# 01_CMUT_TX.net
KiCad netlist of a schematic drawn in Altium Designer
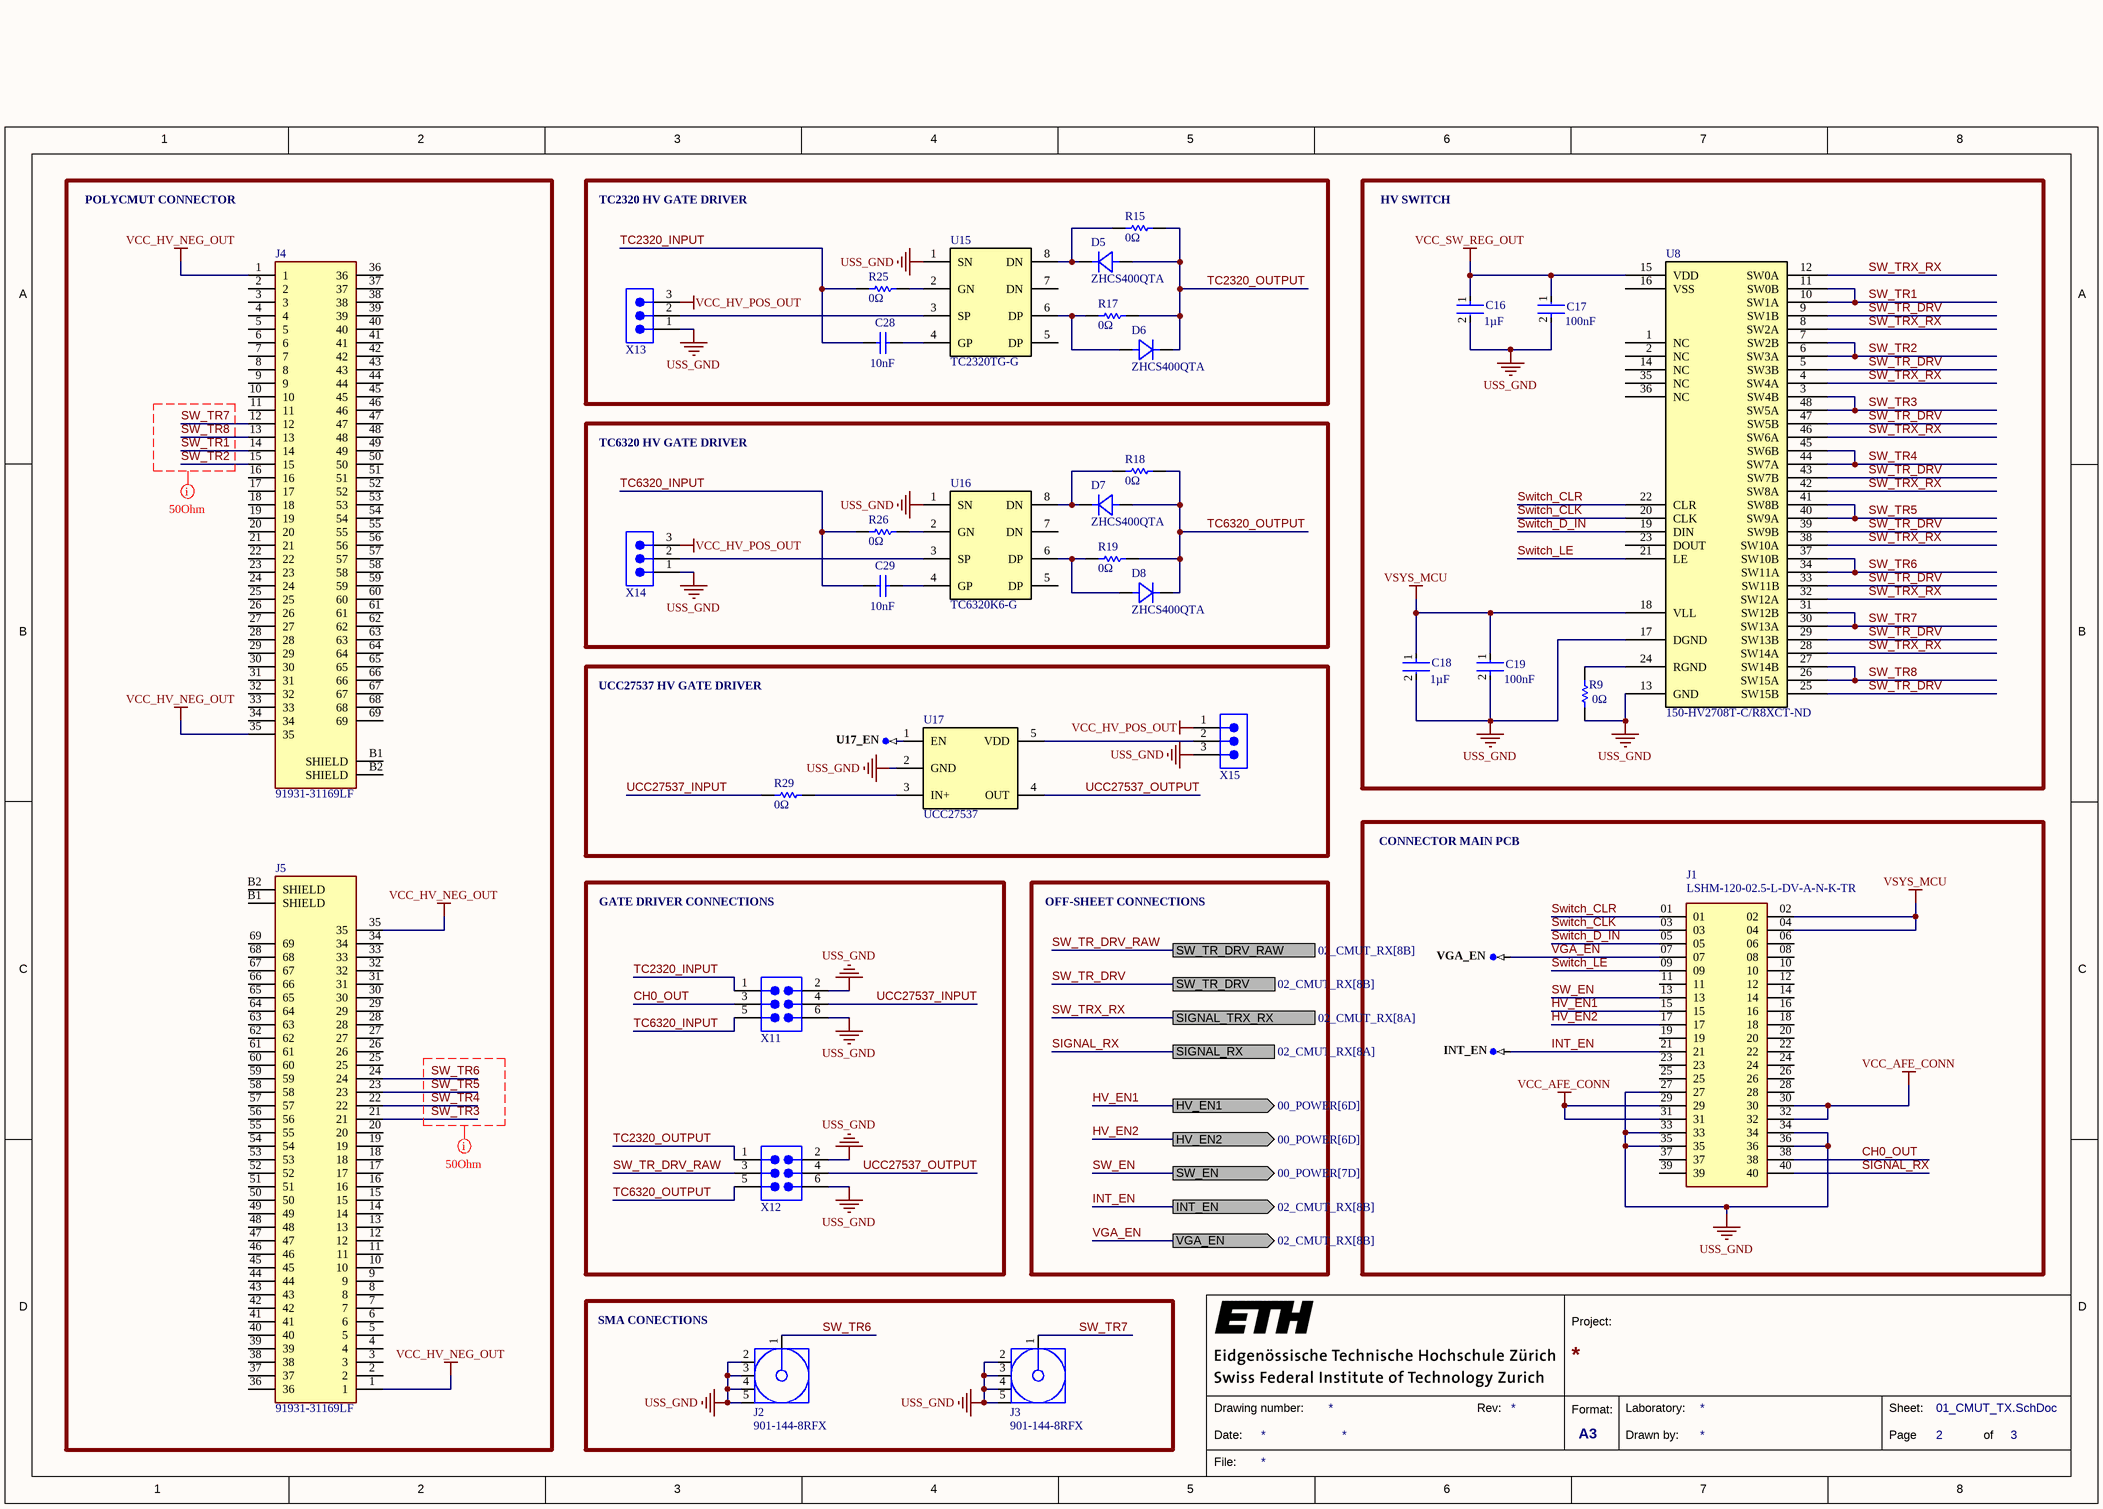
[diagram p0: 01_CMUT_TX.SchDoc]

(export (version "E")
  (design (tool "Eeschema 10.0.6"))
  (components
    (comp (ref "C16")
      (value "CGA3E3X5R1H105K")
      (footprint "FP-CGA3E-0_3-0_1-IPC_B")
      (description "Cap Ceramic 1uF 50V X5R 10% Pad SMD 0603 +85°C Automotive T/R")
      (fields (field (name "TOLERANCE") "10%") (field (name "CAPACITANCE") "1µF"))
      (libsource (lib "Altium Content Vault") (part "b4654b650e69147ec39a6b967a45e02"))
    )
    (comp (ref "C17")
      (value "C1608X5R1H104K080AA")
      (footprint "FP-C1608-080-0_1-MFG")
      (description "Multilayer Ceramic Capacitors 100nF ±10% 50V X5R SMD 0603")
      (fields (field (name "TOLERANCE") "10%") (field (name "CAPACITANCE") "100nF"))
      (libsource (lib "Altium Content Vault") (part "236180d848d6139a670b325ea6854c9"))
    )
    (comp (ref "C18")
      (value "CGA3E3X5R1H105K")
      (footprint "FP-CGA3E-0_3-0_1-IPC_B")
      (description "Cap Ceramic 1uF 50V X5R 10% Pad SMD 0603 +85°C Automotive T/R")
      (fields (field (name "TOLERANCE") "10%") (field (name "CAPACITANCE") "1µF"))
      (libsource (lib "Altium Content Vault") (part "b4654b650e69147ec39a6b967a45e02"))
    )
    (comp (ref "C19")
      (value "C1608X5R1H104K080AA")
      (footprint "FP-C1608-080-0_1-MFG")
      (description "Multilayer Ceramic Capacitors 100nF ±10% 50V X5R SMD 0603")
      (fields (field (name "TOLERANCE") "10%") (field (name "CAPACITANCE") "100nF"))
      (libsource (lib "Altium Content Vault") (part "236180d848d6139a670b325ea6854c9"))
    )
    (comp (ref "C28")
      (value "06035D103KAT2A")
      (footprint "CAPC1608X90X35NL15T15")
      (fields (field (name "MANUFACTURER") "AVX Interconnect / Elco") (field (name "CAPACITANCE") "10nF"))
      (libsource (lib "Altium Content Vault") (part "CAP"))
    )
    (comp (ref "C29")
      (value "06035D103KAT2A")
      (footprint "CAPC1608X90X35NL15T15")
      (fields (field (name "MANUFACTURER") "AVX Interconnect / Elco") (field (name "CAPACITANCE") "10nF"))
      (libsource (lib "Altium Content Vault") (part "CAP"))
    )
    (comp (ref "D5")
      (value "ZHCS400QTA")
      (footprint "DIODE_SOD323_DIO")
      (description "Diode Schottky 40V 1A Automotive 2-Pin SOD-323 T/R")
      (fields (field (name "MANUFACTURER") "Diodes"))
      (libsource (lib "Schlib1") (part "ZHCS400QTA"))
    )
    (comp (ref "D6")
      (value "ZHCS400QTA")
      (footprint "DIODE_SOD323_DIO")
      (description "Diode Schottky 40V 1A Automotive 2-Pin SOD-323 T/R")
      (fields (field (name "MANUFACTURER") "Diodes"))
      (libsource (lib "Schlib1") (part "ZHCS400QTA"))
    )
    (comp (ref "D7")
      (value "ZHCS400QTA")
      (footprint "DIODE_SOD323_DIO")
      (description "Diode Schottky 40V 1A Automotive 2-Pin SOD-323 T/R")
      (fields (field (name "MANUFACTURER") "Diodes"))
      (libsource (lib "Schlib1") (part "ZHCS400QTA"))
    )
    (comp (ref "D8")
      (value "ZHCS400QTA")
      (footprint "DIODE_SOD323_DIO")
      (description "Diode Schottky 40V 1A Automotive 2-Pin SOD-323 T/R")
      (fields (field (name "MANUFACTURER") "Diodes"))
      (libsource (lib "Schlib1") (part "ZHCS400QTA"))
    )
    (comp (ref "INT_EN")
      (value "TP-SM-C-100")
      (footprint "TP-SM-C-100")
      (description "Test Point, Surface Mount, Circular, Pad Diameter 1 mm")
      (fields (field (name "MANUFACTURER") "No Vendor"))
      (libsource (lib "Altium Content Vault") (part "TP-SM"))
    )
    (comp (ref "J1")
      (value "LSHM-120-02.5-L-DV-A-N-K-TR")
      (footprint "SAMTEC_LSHM-120-XX.X-X-DV-A-N-XX")
      (description "Conn Socket and Terminal Strip HDR/SKT 40 POS 0.5mm Solder ST SMD T/R")
      (fields
        (field (name "MANUFACTURER") "Samtec")
        (field (name "MANUFACTURER PART NUMBER") "LSHM-120-02.5-L-DV-A-N-K-TR")
      )
      (libsource (lib "Schlib1") (part "LSHM-120-02.5-L-DV-A-N-K-TR"))
    )
    (comp (ref "J2")
      (value "901-144-8RFX")
      (footprint "AMPH-901-144-8RFX_V")
      (description "Coaxial Connector, 18 GHz, 50 Ohm, -65 to 165 degC, 5-Pin THD, RoHS, Bulk")
      (fields (field (name "MANUFACTURER") "Amphenol"))
      (libsource (lib "Altium Content Vault") (part "CN-S-4F-RF5"))
    )
    (comp (ref "J3")
      (value "901-144-8RFX")
      (footprint "AMPH-901-144-8RFX_V")
      (description "Coaxial Connector, 18 GHz, 50 Ohm, -65 to 165 degC, 5-Pin THD, RoHS, Bulk")
      (fields (field (name "MANUFACTURER") "Amphenol"))
      (libsource (lib "Altium Content Vault") (part "CN-S-4F-RF5"))
    )
    (comp (ref "J4")
      (value "91931-31169LF")
      (footprint "FRAMETOME_91931-31169LF")
      (description "Conn; Rect; Industrial; MezzanineRECP; 69Cnts; SMT; I-IndustrialSeries")
      (libsource (lib "") (part "91931-31169LF_1"))
    )
    (comp (ref "J5")
      (value "91931-31169LF")
      (footprint "FRAMETOME_91931-31169LF")
      (description "Conn; Rect; Industrial; MezzanineRECP; 69Cnts; SMT; I-IndustrialSeries")
      (libsource (lib "91931-31169LF") (part "91931-31169LF"))
    )
    (comp (ref "R9")
      (value "RC0603JR-130RL")
      (footprint "RESC1608X55X25NL10T15")
      (fields (field (name "MANUFACTURER") "Yageo") (field (name "RESISTANCE") "0Ω"))
      (libsource (lib "Altium Content Vault") (part "RES"))
    )
    (comp (ref "R15")
      (value "RC0603JR-130RL")
      (footprint "RESC1608X55X25NL10T15")
      (fields (field (name "MANUFACTURER") "Yageo") (field (name "RESISTANCE") "0Ω"))
      (libsource (lib "Altium Content Vault") (part "RES"))
    )
    (comp (ref "R17")
      (value "RC0603JR-130RL")
      (footprint "RESC1608X55X25NL10T15")
      (fields (field (name "MANUFACTURER") "Yageo") (field (name "RESISTANCE") "0Ω"))
      (libsource (lib "Altium Content Vault") (part "RES"))
    )
    (comp (ref "R18")
      (value "RC0603JR-130RL")
      (footprint "RESC1608X55X25NL10T15")
      (fields (field (name "MANUFACTURER") "Yageo") (field (name "RESISTANCE") "0Ω"))
      (libsource (lib "Altium Content Vault") (part "RES"))
    )
    (comp (ref "R19")
      (value "RC0603JR-130RL")
      (footprint "RESC1608X55X25NL10T15")
      (fields (field (name "MANUFACTURER") "Yageo") (field (name "RESISTANCE") "0Ω"))
      (libsource (lib "Altium Content Vault") (part "RES"))
    )
    (comp (ref "R25")
      (value "RC0603JR-130RL")
      (footprint "RESC1608X55X25NL10T15")
      (fields (field (name "MANUFACTURER") "Yageo") (field (name "RESISTANCE") "0Ω"))
      (libsource (lib "Altium Content Vault") (part "RES"))
    )
    (comp (ref "R26")
      (value "RC0603JR-130RL")
      (footprint "RESC1608X55X25NL10T15")
      (fields (field (name "MANUFACTURER") "Yageo") (field (name "RESISTANCE") "0Ω"))
      (libsource (lib "Altium Content Vault") (part "RES"))
    )
    (comp (ref "R29")
      (value "RC0603JR-130RL")
      (footprint "RESC1608X55X25NL10T15")
      (fields (field (name "MANUFACTURER") "Yageo") (field (name "RESISTANCE") "0Ω"))
      (libsource (lib "Altium Content Vault") (part "RES"))
    )
    (comp (ref "U8")
      (value "HV2708T-C/R8X")
      (footprint "LQFP48_7X7MC_MCH")
      (description "16-CH 200V No Hv Bias Switch (SPST), 1 Bleed Resistor 48 LQFP 7X7X1.4MM T/r Rohs Compliant: Yes")
      (fields
        (field (name "MANUFACTURER") "Microchip")
        (field (name "SUPPLIER PART NUMBER 1") "150-HV2708T-C/R8XCT-ND")
      )
      (libsource (lib "Schlib1") (part "HV2708T-C/R8X"))
    )
    (comp (ref "U15")
      (value "TC2320TG-G")
      (footprint "SOIC127P599X173-8N")
      (description "8L SOIC N-Channel and P-Channel Enhancement-Mode Dual MOSFET")
      (libsource (lib "Schlib1") (part "TC2320"))
    )
    (comp (ref "U16")
      (value "TC6320K6-G")
      (footprint "SOIC127P599X173-8N")
      (description "8L SOIC N-Channel and P-Channel Enhancement-Mode Dual MOSFET")
      (libsource (lib "Schlib1") (part "TC2320"))
    )
    (comp (ref "U17")
      (value "UCC27537")
      (footprint "SOT95P280X145-5N")
      (description "5P SOT-23 DBV MOSFET IGBT Single-Gate-Driver")
      (libsource (lib "Schlib1") (part "UCC27537"))
    )
    (comp (ref "U17_EN")
      (value "TP-SM-C-100")
      (footprint "TP-SM-C-100")
      (description "Test Point, Surface Mount, Circular, Pad Diameter 1 mm")
      (fields (field (name "MANUFACTURER") "No Vendor"))
      (libsource (lib "Altium Content Vault") (part "TP-SM"))
    )
    (comp (ref "VGA_EN")
      (value "TP-SM-C-100")
      (footprint "TP-SM-C-100")
      (description "Test Point, Surface Mount, Circular, Pad Diameter 1 mm")
      (fields (field (name "MANUFACTURER") "No Vendor"))
      (libsource (lib "Altium Content Vault") (part "TP-SM"))
    )
    (comp (ref "X11")
      (value "67996-106HLF")
      (footprint "67996-106HLF")
      (description "6 Positions Header, Unshrouded Connector 0.100\" (2.54mm) Through Hole Gold or Gold, GXT™")
      (fields (field (name "MANUFACTURER") "Amphenol FCI"))
      (libsource (lib "ETHZ Vault") (part "CON-3x2-Male"))
    )
    (comp (ref "X12")
      (value "67996-106HLF")
      (footprint "67996-106HLF")
      (description "6 Positions Header, Unshrouded Connector 0.100\" (2.54mm) Through Hole Gold or Gold, GXT™")
      (fields (field (name "MANUFACTURER") "Amphenol FCI"))
      (libsource (lib "ETHZ Vault") (part "CON-3x2-Male"))
    )
    (comp (ref "X13")
      (value "68000-103HLF")
      (footprint "68000-103HLF")
      (description "3 Positions Header, Unshrouded Connector 0.100\" (2.54mm) Through Hole Gold or Gold, GXT™")
      (fields (field (name "MANUFACTURER") "Amphenol FCI"))
      (libsource (lib "ETHZ Vault") (part "CON-1x3-Male"))
    )
    (comp (ref "X14")
      (value "68000-103HLF")
      (footprint "68000-103HLF")
      (description "3 Positions Header, Unshrouded Connector 0.100\" (2.54mm) Through Hole Gold or Gold, GXT™")
      (fields (field (name "MANUFACTURER") "Amphenol FCI"))
      (libsource (lib "ETHZ Vault") (part "CON-1x3-Male"))
    )
    (comp (ref "X15")
      (value "68000-103HLF")
      (footprint "68000-103HLF")
      (description "3 Positions Header, Unshrouded Connector 0.100\" (2.54mm) Through Hole Gold or Gold, GXT™")
      (fields (field (name "MANUFACTURER") "Amphenol FCI"))
      (libsource (lib "ETHZ Vault") (part "CON-1x3-Male"))
    )
  )
  (nets
    (net (code "2") (name "/CH0_OUT") (class "Default")
      (node (ref "J1") (pin "38") (pinfunction "38_38") (pintype "passive"))
      (node (ref "X11") (pin "3") (pinfunction "3_3") (pintype "passive"))
    )
    (net (code "3") (name "/HV_EN1") (class "Default")
      (node (ref "J1") (pin "15") (pinfunction "15_15") (pintype "passive"))
    )
    (net (code "4") (name "/HV_EN2") (class "Default")
      (node (ref "J1") (pin "17") (pinfunction "17_17") (pintype "passive"))
    )
    (net (code "5") (name "/INT_EN") (class "Default")
      (node (ref "INT_EN") (pin "1") (pinfunction "1_1") (pintype "input"))
      (node (ref "J1") (pin "21") (pinfunction "21_21") (pintype "passive"))
    )
    (net (code "6") (name "/SIGNAL_RX") (class "Default")
      (node (ref "J1") (pin "40") (pinfunction "40_40") (pintype "passive"))
    )
    (net (code "7") (name "/SW_EN") (class "Default")
      (node (ref "J1") (pin "13") (pinfunction "13_13") (pintype "passive"))
    )
    (net (code "8") (name "/SW_TR1") (class "Default")
      (node (ref "J4") (pin "14") (pinfunction "14_14") (pintype "passive"))
      (node (ref "U8") (pin "10") (pinfunction "SW1A_10") (pintype "passive"))
      (node (ref "U8") (pin "11") (pinfunction "SW0B_11") (pintype "passive"))
    )
    (net (code "9") (name "/SW_TR2") (class "Default")
      (node (ref "J4") (pin "15") (pinfunction "15_15") (pintype "passive"))
      (node (ref "U8") (pin "6") (pinfunction "SW3A_6") (pintype "passive"))
      (node (ref "U8") (pin "7") (pinfunction "SW2B_7") (pintype "passive"))
    )
    (net (code "10") (name "/SW_TR3") (class "Default")
      (node (ref "J5") (pin "21") (pinfunction "21_21") (pintype "passive"))
      (node (ref "U8") (pin "3") (pinfunction "SW4B_3") (pintype "passive"))
      (node (ref "U8") (pin "48") (pinfunction "SW5A_48") (pintype "passive"))
    )
    (net (code "11") (name "/SW_TR4") (class "Default")
      (node (ref "J5") (pin "22") (pinfunction "22_22") (pintype "passive"))
      (node (ref "U8") (pin "44") (pinfunction "SW7A_44") (pintype "passive"))
      (node (ref "U8") (pin "45") (pinfunction "SW6B_45") (pintype "passive"))
    )
    (net (code "12") (name "/SW_TR5") (class "Default")
      (node (ref "J5") (pin "23") (pinfunction "23_23") (pintype "passive"))
      (node (ref "U8") (pin "40") (pinfunction "SW9A_40") (pintype "passive"))
      (node (ref "U8") (pin "41") (pinfunction "SW8B_41") (pintype "passive"))
    )
    (net (code "13") (name "/SW_TR6") (class "Default")
      (node (ref "J2") (pin "1") (pinfunction "1_1") (pintype "passive"))
      (node (ref "J5") (pin "24") (pinfunction "24_24") (pintype "passive"))
      (node (ref "U8") (pin "34") (pinfunction "SW11A_34") (pintype "passive"))
      (node (ref "U8") (pin "37") (pinfunction "SW10B_37") (pintype "passive"))
    )
    (net (code "14") (name "/SW_TR7") (class "Default")
      (node (ref "J3") (pin "1") (pinfunction "1_1") (pintype "passive"))
      (node (ref "J4") (pin "12") (pinfunction "12_12") (pintype "passive"))
      (node (ref "U8") (pin "30") (pinfunction "SW13A_30") (pintype "passive"))
      (node (ref "U8") (pin "31") (pinfunction "SW12B_31") (pintype "passive"))
    )
    (net (code "15") (name "/SW_TR8") (class "Default")
      (node (ref "J4") (pin "13") (pinfunction "13_13") (pintype "passive"))
      (node (ref "U8") (pin "26") (pinfunction "SW15A_26") (pintype "passive"))
      (node (ref "U8") (pin "27") (pinfunction "SW14B_27") (pintype "passive"))
    )
    (net (code "16") (name "/SW_TRX_RX") (class "Default")
      (node (ref "U8") (pin "12") (pinfunction "SW0A_12") (pintype "passive"))
      (node (ref "U8") (pin "28") (pinfunction "SW14A_28") (pintype "passive"))
      (node (ref "U8") (pin "32") (pinfunction "SW12A_32") (pintype "passive"))
      (node (ref "U8") (pin "38") (pinfunction "SW10A_38") (pintype "passive"))
      (node (ref "U8") (pin "4") (pinfunction "SW4A_4") (pintype "passive"))
      (node (ref "U8") (pin "42") (pinfunction "SW8A_42") (pintype "passive"))
      (node (ref "U8") (pin "46") (pinfunction "SW6A_46") (pintype "passive"))
      (node (ref "U8") (pin "8") (pinfunction "SW2A_8") (pintype "passive"))
    )
    (net (code "17") (name "/SW_TR_DRV") (class "Default")
      (node (ref "U8") (pin "25") (pinfunction "SW15B_25") (pintype "passive"))
      (node (ref "U8") (pin "29") (pinfunction "SW13B_29") (pintype "passive"))
      (node (ref "U8") (pin "33") (pinfunction "SW11B_33") (pintype "passive"))
      (node (ref "U8") (pin "39") (pinfunction "SW9B_39") (pintype "passive"))
      (node (ref "U8") (pin "43") (pinfunction "SW7B_43") (pintype "passive"))
      (node (ref "U8") (pin "47") (pinfunction "SW5B_47") (pintype "passive"))
      (node (ref "U8") (pin "5") (pinfunction "SW3B_5") (pintype "passive"))
      (node (ref "U8") (pin "9") (pinfunction "SW1B_9") (pintype "passive"))
    )
    (net (code "18") (name "/SW_TR_DRV_RAW") (class "Default")
      (node (ref "X12") (pin "3") (pinfunction "3_3") (pintype "passive"))
    )
    (net (code "19") (name "/Switch_CLK") (class "Default")
      (node (ref "J1") (pin "03") (pinfunction "03_03") (pintype "passive"))
      (node (ref "U8") (pin "20") (pinfunction "CLK_20") (pintype "passive"))
    )
    (net (code "20") (name "/Switch_CLR") (class "Default")
      (node (ref "J1") (pin "01") (pinfunction "01_01") (pintype "passive"))
      (node (ref "U8") (pin "22") (pinfunction "CLR_22") (pintype "passive"))
    )
    (net (code "21") (name "/Switch_D_IN") (class "Default")
      (node (ref "J1") (pin "05") (pinfunction "05_05") (pintype "passive"))
      (node (ref "U8") (pin "19") (pinfunction "DIN_19") (pintype "passive"))
    )
    (net (code "22") (name "/Switch_LE") (class "Default")
      (node (ref "J1") (pin "09") (pinfunction "09_09") (pintype "passive"))
      (node (ref "U8") (pin "21") (pinfunction "LE_21") (pintype "passive"))
    )
    (net (code "23") (name "/TC2320_INPUT") (class "Default")
      (node (ref "C28") (pin "1") (pinfunction "1_1") (pintype "passive"))
      (node (ref "R25") (pin "2") (pinfunction "2_2") (pintype "passive"))
      (node (ref "X11") (pin "1") (pinfunction "1_1") (pintype "passive"))
    )
    (net (code "24") (name "/TC2320_OUTPUT") (class "Default")
      (node (ref "D5") (pin "2") (pinfunction "2_2") (pintype "passive"))
      (node (ref "D6") (pin "1") (pinfunction "1_1") (pintype "passive"))
      (node (ref "R15") (pin "1") (pinfunction "1_1") (pintype "passive"))
      (node (ref "R17") (pin "1") (pinfunction "1_1") (pintype "passive"))
      (node (ref "X12") (pin "1") (pinfunction "1_1") (pintype "passive"))
    )
    (net (code "25") (name "/TC6320_INPUT") (class "Default")
      (node (ref "C29") (pin "1") (pinfunction "1_1") (pintype "passive"))
      (node (ref "R26") (pin "2") (pinfunction "2_2") (pintype "passive"))
      (node (ref "X11") (pin "5") (pinfunction "5_5") (pintype "passive"))
    )
    (net (code "26") (name "/TC6320_OUTPUT") (class "Default")
      (node (ref "D7") (pin "2") (pinfunction "2_2") (pintype "passive"))
      (node (ref "D8") (pin "1") (pinfunction "1_1") (pintype "passive"))
      (node (ref "R18") (pin "1") (pinfunction "1_1") (pintype "passive"))
      (node (ref "R19") (pin "1") (pinfunction "1_1") (pintype "passive"))
      (node (ref "X12") (pin "5") (pinfunction "5_5") (pintype "passive"))
    )
    (net (code "27") (name "/UCC27537_INPUT") (class "Default")
      (node (ref "R29") (pin "2") (pinfunction "2_2") (pintype "passive"))
      (node (ref "X11") (pin "4") (pinfunction "4_4") (pintype "passive"))
    )
    (net (code "28") (name "/UCC27537_OUTPUT") (class "Default")
      (node (ref "U17") (pin "4") (pinfunction "OUT_4") (pintype "power_in"))
      (node (ref "X12") (pin "4") (pinfunction "4_4") (pintype "passive"))
    )
    (net (code "29") (name "/VGA_EN") (class "Default")
      (node (ref "J1") (pin "07") (pinfunction "07_07") (pintype "passive"))
      (node (ref "VGA_EN") (pin "1") (pinfunction "1_1") (pintype "input"))
    )
    (net (code "30") (name "Net-(D5-Pad1)") (class "Default")
      (node (ref "D5") (pin "1") (pinfunction "1_1") (pintype "passive"))
      (node (ref "R15") (pin "2") (pinfunction "2_2") (pintype "passive"))
      (node (ref "U15") (pin "8") (pinfunction "DN_8") (pintype "power_in"))
    )
    (net (code "31") (name "Net-(D6-Pad2)") (class "Default")
      (node (ref "D6") (pin "2") (pinfunction "2_2") (pintype "passive"))
      (node (ref "R17") (pin "2") (pinfunction "2_2") (pintype "passive"))
      (node (ref "U15") (pin "6") (pinfunction "DP_6") (pintype "power_in"))
    )
    (net (code "32") (name "Net-(D7-Pad1)") (class "Default")
      (node (ref "D7") (pin "1") (pinfunction "1_1") (pintype "passive"))
      (node (ref "R18") (pin "2") (pinfunction "2_2") (pintype "passive"))
      (node (ref "U16") (pin "8") (pinfunction "DN_8") (pintype "power_in"))
    )
    (net (code "33") (name "Net-(D8-Pad2)") (class "Default")
      (node (ref "D8") (pin "2") (pinfunction "2_2") (pintype "passive"))
      (node (ref "R19") (pin "2") (pinfunction "2_2") (pintype "passive"))
      (node (ref "U16") (pin "6") (pinfunction "DP_6") (pintype "power_in"))
    )
    (net (code "34") (name "Net-(U8-RGND)") (class "Default")
      (node (ref "R9") (pin "2") (pinfunction "2_2") (pintype "passive"))
      (node (ref "U8") (pin "24") (pinfunction "RGND_24") (pintype "passive"))
    )
    (net (code "35") (name "Net-(U15-GN)") (class "Default")
      (node (ref "R25") (pin "1") (pinfunction "1_1") (pintype "passive"))
      (node (ref "U15") (pin "2") (pinfunction "GN_2") (pintype "power_in"))
    )
    (net (code "36") (name "Net-(U15-GP)") (class "Default")
      (node (ref "C28") (pin "2") (pinfunction "2_2") (pintype "passive"))
      (node (ref "U15") (pin "4") (pinfunction "GP_4") (pintype "open_collector"))
    )
    (net (code "37") (name "Net-(U15-SP)") (class "Default")
      (node (ref "U15") (pin "3") (pinfunction "SP_3") (pintype "power_in"))
      (node (ref "X13") (pin "2") (pinfunction "2_2") (pintype "passive"))
    )
    (net (code "38") (name "Net-(U16-GN)") (class "Default")
      (node (ref "R26") (pin "1") (pinfunction "1_1") (pintype "passive"))
      (node (ref "U16") (pin "2") (pinfunction "GN_2") (pintype "power_in"))
    )
    (net (code "39") (name "Net-(U16-GP)") (class "Default")
      (node (ref "C29") (pin "2") (pinfunction "2_2") (pintype "passive"))
      (node (ref "U16") (pin "4") (pinfunction "GP_4") (pintype "open_collector"))
    )
    (net (code "40") (name "Net-(U16-SP)") (class "Default")
      (node (ref "U16") (pin "3") (pinfunction "SP_3") (pintype "power_in"))
      (node (ref "X14") (pin "2") (pinfunction "2_2") (pintype "passive"))
    )
    (net (code "41") (name "Net-(U17-EN)") (class "Default")
      (node (ref "U17") (pin "1") (pinfunction "EN_1") (pintype "power_in"))
      (node (ref "U17_EN") (pin "1") (pinfunction "1_1") (pintype "input"))
    )
    (net (code "42") (name "Net-(U17-IN+)") (class "Default")
      (node (ref "R29") (pin "1") (pinfunction "1_1") (pintype "passive"))
      (node (ref "U17") (pin "3") (pinfunction "IN+_3") (pintype "power_in"))
    )
    (net (code "43") (name "Net-(U17-VDD)") (class "Default")
      (node (ref "U17") (pin "5") (pinfunction "VDD_5") (pintype "power_in"))
      (node (ref "X15") (pin "2") (pinfunction "2_2") (pintype "passive"))
    )
    (net (code "44") (name "USS_GND") (class "Default")
      (node (ref "C16") (pin "2") (pinfunction "2_2") (pintype "passive"))
      (node (ref "C17") (pin "2") (pinfunction "2_2") (pintype "passive"))
      (node (ref "C18") (pin "2") (pinfunction "2_2") (pintype "passive"))
      (node (ref "C19") (pin "2") (pinfunction "2_2") (pintype "passive"))
      (node (ref "J1") (pin "27") (pinfunction "27_27") (pintype "passive"))
      (node (ref "J1") (pin "33") (pinfunction "33_33") (pintype "passive"))
      (node (ref "J1") (pin "34") (pinfunction "34_34") (pintype "passive"))
      (node (ref "J1") (pin "35") (pinfunction "35_35") (pintype "passive"))
      (node (ref "J1") (pin "36") (pinfunction "36_36") (pintype "passive"))
      (node (ref "J2") (pin "2") (pinfunction "2_2") (pintype "passive"))
      (node (ref "J2") (pin "3") (pinfunction "3_3") (pintype "passive"))
      (node (ref "J2") (pin "4") (pinfunction "4_4") (pintype "passive"))
      (node (ref "J2") (pin "5") (pinfunction "5_5") (pintype "passive"))
      (node (ref "J3") (pin "2") (pinfunction "2_2") (pintype "passive"))
      (node (ref "J3") (pin "3") (pinfunction "3_3") (pintype "passive"))
      (node (ref "J3") (pin "4") (pinfunction "4_4") (pintype "passive"))
      (node (ref "J3") (pin "5") (pinfunction "5_5") (pintype "passive"))
      (node (ref "R9") (pin "1") (pinfunction "1_1") (pintype "passive"))
      (node (ref "U15") (pin "1") (pinfunction "SN_1") (pintype "power_in"))
      (node (ref "U16") (pin "1") (pinfunction "SN_1") (pintype "power_in"))
      (node (ref "U17") (pin "2") (pinfunction "GND_2") (pintype "power_in"))
      (node (ref "U8") (pin "13") (pinfunction "GND_13") (pintype "passive"))
      (node (ref "U8") (pin "17") (pinfunction "DGND_17") (pintype "passive"))
      (node (ref "X11") (pin "2") (pinfunction "2_2") (pintype "passive"))
      (node (ref "X11") (pin "6") (pinfunction "6_6") (pintype "passive"))
      (node (ref "X12") (pin "2") (pinfunction "2_2") (pintype "passive"))
      (node (ref "X12") (pin "6") (pinfunction "6_6") (pintype "passive"))
      (node (ref "X13") (pin "1") (pinfunction "1_1") (pintype "passive"))
      (node (ref "X14") (pin "1") (pinfunction "1_1") (pintype "passive"))
      (node (ref "X15") (pin "3") (pinfunction "3_3") (pintype "passive"))
    )
    (net (code "45") (name "VCC_AFE_CONN") (class "Default")
      (node (ref "J1") (pin "29") (pinfunction "29_29") (pintype "passive"))
      (node (ref "J1") (pin "30") (pinfunction "30_30") (pintype "passive"))
      (node (ref "J1") (pin "31") (pinfunction "31_31") (pintype "passive"))
      (node (ref "J1") (pin "32") (pinfunction "32_32") (pintype "passive"))
    )
    (net (code "46") (name "VCC_HV_NEG_OUT") (class "Default")
      (node (ref "J4") (pin "1") (pinfunction "1_1") (pintype "passive"))
      (node (ref "J4") (pin "35") (pinfunction "35_35") (pintype "passive"))
      (node (ref "J5") (pin "1") (pinfunction "1_1") (pintype "passive"))
      (node (ref "J5") (pin "35") (pinfunction "35_35") (pintype "passive"))
    )
    (net (code "47") (name "VCC_HV_POS_OUT") (class "Default")
      (node (ref "X13") (pin "3") (pinfunction "3_3") (pintype "passive"))
      (node (ref "X14") (pin "3") (pinfunction "3_3") (pintype "passive"))
      (node (ref "X15") (pin "1") (pinfunction "1_1") (pintype "passive"))
    )
    (net (code "48") (name "VCC_SW_REG_OUT") (class "Default")
      (node (ref "C16") (pin "1") (pinfunction "1_1") (pintype "passive"))
      (node (ref "C17") (pin "1") (pinfunction "1_1") (pintype "passive"))
      (node (ref "U8") (pin "15") (pinfunction "VDD_15") (pintype "passive"))
    )
    (net (code "49") (name "VSYS_MCU") (class "Default")
      (node (ref "C18") (pin "1") (pinfunction "1_1") (pintype "passive"))
      (node (ref "C19") (pin "1") (pinfunction "1_1") (pintype "passive"))
      (node (ref "J1") (pin "02") (pinfunction "02_02") (pintype "passive"))
      (node (ref "J1") (pin "04") (pinfunction "04_04") (pintype "passive"))
      (node (ref "U8") (pin "18") (pinfunction "VLL_18") (pintype "passive"))
    )
    (net (code "50") (name "unconnected-(J1-Pad06)") (class "Default")
      (node (ref "J1") (pin "06") (pinfunction "06_06") (pintype "passive"))
    )
    (net (code "51") (name "unconnected-(J1-Pad08)") (class "Default")
      (node (ref "J1") (pin "08") (pinfunction "08_08") (pintype "passive"))
    )
    (net (code "52") (name "unconnected-(J1-Pad10)") (class "Default")
      (node (ref "J1") (pin "10") (pinfunction "10_10") (pintype "passive"))
    )
    (net (code "53") (name "unconnected-(J1-Pad11)") (class "Default")
      (node (ref "J1") (pin "11") (pinfunction "11_11") (pintype "passive"))
    )
    (net (code "54") (name "unconnected-(J1-Pad12)") (class "Default")
      (node (ref "J1") (pin "12") (pinfunction "12_12") (pintype "passive"))
    )
    (net (code "55") (name "unconnected-(J1-Pad14)") (class "Default")
      (node (ref "J1") (pin "14") (pinfunction "14_14") (pintype "passive"))
    )
    (net (code "56") (name "unconnected-(J1-Pad16)") (class "Default")
      (node (ref "J1") (pin "16") (pinfunction "16_16") (pintype "passive"))
    )
    (net (code "57") (name "unconnected-(J1-Pad18)") (class "Default")
      (node (ref "J1") (pin "18") (pinfunction "18_18") (pintype "passive"))
    )
    (net (code "58") (name "unconnected-(J1-Pad19)") (class "Default")
      (node (ref "J1") (pin "19") (pinfunction "19_19") (pintype "passive"))
    )
    (net (code "59") (name "unconnected-(J1-Pad20)") (class "Default")
      (node (ref "J1") (pin "20") (pinfunction "20_20") (pintype "passive"))
    )
    (net (code "60") (name "unconnected-(J1-Pad22)") (class "Default")
      (node (ref "J1") (pin "22") (pinfunction "22_22") (pintype "passive"))
    )
    (net (code "61") (name "unconnected-(J1-Pad23)") (class "Default")
      (node (ref "J1") (pin "23") (pinfunction "23_23") (pintype "passive"))
    )
    (net (code "62") (name "unconnected-(J1-Pad24)") (class "Default")
      (node (ref "J1") (pin "24") (pinfunction "24_24") (pintype "passive"))
    )
    (net (code "63") (name "unconnected-(J1-Pad25)") (class "Default")
      (node (ref "J1") (pin "25") (pinfunction "25_25") (pintype "passive"))
    )
    (net (code "64") (name "unconnected-(J1-Pad26)") (class "Default")
      (node (ref "J1") (pin "26") (pinfunction "26_26") (pintype "passive"))
    )
    (net (code "65") (name "unconnected-(J1-Pad28)") (class "Default")
      (node (ref "J1") (pin "28") (pinfunction "28_28") (pintype "passive"))
    )
    (net (code "66") (name "unconnected-(J1-Pad37)") (class "Default")
      (node (ref "J1") (pin "37") (pinfunction "37_37") (pintype "passive"))
    )
    (net (code "67") (name "unconnected-(J1-Pad39)") (class "Default")
      (node (ref "J1") (pin "39") (pinfunction "39_39") (pintype "passive"))
    )
    (net (code "68") (name "unconnected-(J4-Pad2)") (class "Default")
      (node (ref "J4") (pin "2") (pinfunction "2_2") (pintype "passive"))
    )
    (net (code "69") (name "unconnected-(J4-Pad3)") (class "Default")
      (node (ref "J4") (pin "3") (pinfunction "3_3") (pintype "passive"))
    )
    (net (code "70") (name "unconnected-(J4-Pad4)") (class "Default")
      (node (ref "J4") (pin "4") (pinfunction "4_4") (pintype "passive"))
    )
    (net (code "71") (name "unconnected-(J4-Pad5)") (class "Default")
      (node (ref "J4") (pin "5") (pinfunction "5_5") (pintype "passive"))
    )
    (net (code "72") (name "unconnected-(J4-Pad6)") (class "Default")
      (node (ref "J4") (pin "6") (pinfunction "6_6") (pintype "passive"))
    )
    (net (code "73") (name "unconnected-(J4-Pad7)") (class "Default")
      (node (ref "J4") (pin "7") (pinfunction "7_7") (pintype "passive"))
    )
    (net (code "74") (name "unconnected-(J4-Pad8)") (class "Default")
      (node (ref "J4") (pin "8") (pinfunction "8_8") (pintype "passive"))
    )
    (net (code "75") (name "unconnected-(J4-Pad9)") (class "Default")
      (node (ref "J4") (pin "9") (pinfunction "9_9") (pintype "passive"))
    )
    (net (code "76") (name "unconnected-(J4-Pad10)") (class "Default")
      (node (ref "J4") (pin "10") (pinfunction "10_10") (pintype "passive"))
    )
    (net (code "77") (name "unconnected-(J4-Pad11)") (class "Default")
      (node (ref "J4") (pin "11") (pinfunction "11_11") (pintype "passive"))
    )
    (net (code "78") (name "unconnected-(J4-Pad16)") (class "Default")
      (node (ref "J4") (pin "16") (pinfunction "16_16") (pintype "passive"))
    )
    (net (code "79") (name "unconnected-(J4-Pad17)") (class "Default")
      (node (ref "J4") (pin "17") (pinfunction "17_17") (pintype "passive"))
    )
    (net (code "80") (name "unconnected-(J4-Pad18)") (class "Default")
      (node (ref "J4") (pin "18") (pinfunction "18_18") (pintype "passive"))
    )
    (net (code "81") (name "unconnected-(J4-Pad19)") (class "Default")
      (node (ref "J4") (pin "19") (pinfunction "19_19") (pintype "passive"))
    )
    (net (code "82") (name "unconnected-(J4-Pad20)") (class "Default")
      (node (ref "J4") (pin "20") (pinfunction "20_20") (pintype "passive"))
    )
    (net (code "83") (name "unconnected-(J4-Pad21)") (class "Default")
      (node (ref "J4") (pin "21") (pinfunction "21_21") (pintype "passive"))
    )
    (net (code "84") (name "unconnected-(J4-Pad22)") (class "Default")
      (node (ref "J4") (pin "22") (pinfunction "22_22") (pintype "passive"))
    )
    (net (code "85") (name "unconnected-(J4-Pad23)") (class "Default")
      (node (ref "J4") (pin "23") (pinfunction "23_23") (pintype "passive"))
    )
    (net (code "86") (name "unconnected-(J4-Pad24)") (class "Default")
      (node (ref "J4") (pin "24") (pinfunction "24_24") (pintype "passive"))
    )
    (net (code "87") (name "unconnected-(J4-Pad25)") (class "Default")
      (node (ref "J4") (pin "25") (pinfunction "25_25") (pintype "passive"))
    )
    (net (code "88") (name "unconnected-(J4-Pad26)") (class "Default")
      (node (ref "J4") (pin "26") (pinfunction "26_26") (pintype "passive"))
    )
    (net (code "89") (name "unconnected-(J4-Pad27)") (class "Default")
      (node (ref "J4") (pin "27") (pinfunction "27_27") (pintype "passive"))
    )
    (net (code "90") (name "unconnected-(J4-Pad28)") (class "Default")
      (node (ref "J4") (pin "28") (pinfunction "28_28") (pintype "passive"))
    )
    (net (code "91") (name "unconnected-(J4-Pad29)") (class "Default")
      (node (ref "J4") (pin "29") (pinfunction "29_29") (pintype "passive"))
    )
    (net (code "92") (name "unconnected-(J4-Pad30)") (class "Default")
      (node (ref "J4") (pin "30") (pinfunction "30_30") (pintype "passive"))
    )
    (net (code "93") (name "unconnected-(J4-Pad31)") (class "Default")
      (node (ref "J4") (pin "31") (pinfunction "31_31") (pintype "passive"))
    )
    (net (code "94") (name "unconnected-(J4-Pad32)") (class "Default")
      (node (ref "J4") (pin "32") (pinfunction "32_32") (pintype "passive"))
    )
    (net (code "95") (name "unconnected-(J4-Pad33)") (class "Default")
      (node (ref "J4") (pin "33") (pinfunction "33_33") (pintype "passive"))
    )
    (net (code "96") (name "unconnected-(J4-Pad34)") (class "Default")
      (node (ref "J4") (pin "34") (pinfunction "34_34") (pintype "passive"))
    )
    (net (code "97") (name "unconnected-(J4-Pad36)") (class "Default")
      (node (ref "J4") (pin "36") (pinfunction "36_36") (pintype "passive"))
    )
    (net (code "98") (name "unconnected-(J4-Pad37)") (class "Default")
      (node (ref "J4") (pin "37") (pinfunction "37_37") (pintype "passive"))
    )
    (net (code "99") (name "unconnected-(J4-Pad38)") (class "Default")
      (node (ref "J4") (pin "38") (pinfunction "38_38") (pintype "passive"))
    )
    (net (code "100") (name "unconnected-(J4-Pad39)") (class "Default")
      (node (ref "J4") (pin "39") (pinfunction "39_39") (pintype "passive"))
    )
    (net (code "101") (name "unconnected-(J4-Pad40)") (class "Default")
      (node (ref "J4") (pin "40") (pinfunction "40_40") (pintype "passive"))
    )
    (net (code "102") (name "unconnected-(J4-Pad41)") (class "Default")
      (node (ref "J4") (pin "41") (pinfunction "41_41") (pintype "passive"))
    )
    (net (code "103") (name "unconnected-(J4-Pad42)") (class "Default")
      (node (ref "J4") (pin "42") (pinfunction "42_42") (pintype "passive"))
    )
    (net (code "104") (name "unconnected-(J4-Pad43)") (class "Default")
      (node (ref "J4") (pin "43") (pinfunction "43_43") (pintype "passive"))
    )
    (net (code "105") (name "unconnected-(J4-Pad44)") (class "Default")
      (node (ref "J4") (pin "44") (pinfunction "44_44") (pintype "passive"))
    )
    (net (code "106") (name "unconnected-(J4-Pad45)") (class "Default")
      (node (ref "J4") (pin "45") (pinfunction "45_45") (pintype "passive"))
    )
    (net (code "107") (name "unconnected-(J4-Pad46)") (class "Default")
      (node (ref "J4") (pin "46") (pinfunction "46_46") (pintype "passive"))
    )
    (net (code "108") (name "unconnected-(J4-Pad47)") (class "Default")
      (node (ref "J4") (pin "47") (pinfunction "47_47") (pintype "passive"))
    )
    (net (code "109") (name "unconnected-(J4-Pad48)") (class "Default")
      (node (ref "J4") (pin "48") (pinfunction "48_48") (pintype "passive"))
    )
    (net (code "110") (name "unconnected-(J4-Pad49)") (class "Default")
      (node (ref "J4") (pin "49") (pinfunction "49_49") (pintype "passive"))
    )
    (net (code "111") (name "unconnected-(J4-Pad50)") (class "Default")
      (node (ref "J4") (pin "50") (pinfunction "50_50") (pintype "passive"))
    )
    (net (code "112") (name "unconnected-(J4-Pad51)") (class "Default")
      (node (ref "J4") (pin "51") (pinfunction "51_51") (pintype "passive"))
    )
    (net (code "113") (name "unconnected-(J4-Pad52)") (class "Default")
      (node (ref "J4") (pin "52") (pinfunction "52_52") (pintype "passive"))
    )
    (net (code "114") (name "unconnected-(J4-Pad53)") (class "Default")
      (node (ref "J4") (pin "53") (pinfunction "53_53") (pintype "passive"))
    )
    (net (code "115") (name "unconnected-(J4-Pad54)") (class "Default")
      (node (ref "J4") (pin "54") (pinfunction "54_54") (pintype "passive"))
    )
    (net (code "116") (name "unconnected-(J4-Pad55)") (class "Default")
      (node (ref "J4") (pin "55") (pinfunction "55_55") (pintype "passive"))
    )
    (net (code "117") (name "unconnected-(J4-Pad56)") (class "Default")
      (node (ref "J4") (pin "56") (pinfunction "56_56") (pintype "passive"))
    )
    (net (code "118") (name "unconnected-(J4-Pad57)") (class "Default")
      (node (ref "J4") (pin "57") (pinfunction "57_57") (pintype "passive"))
    )
    (net (code "119") (name "unconnected-(J4-Pad58)") (class "Default")
      (node (ref "J4") (pin "58") (pinfunction "58_58") (pintype "passive"))
    )
    (net (code "120") (name "unconnected-(J4-Pad59)") (class "Default")
      (node (ref "J4") (pin "59") (pinfunction "59_59") (pintype "passive"))
    )
    (net (code "121") (name "unconnected-(J4-Pad60)") (class "Default")
      (node (ref "J4") (pin "60") (pinfunction "60_60") (pintype "passive"))
    )
    (net (code "122") (name "unconnected-(J4-Pad61)") (class "Default")
      (node (ref "J4") (pin "61") (pinfunction "61_61") (pintype "passive"))
    )
    (net (code "123") (name "unconnected-(J4-Pad62)") (class "Default")
      (node (ref "J4") (pin "62") (pinfunction "62_62") (pintype "passive"))
    )
    (net (code "124") (name "unconnected-(J4-Pad63)") (class "Default")
      (node (ref "J4") (pin "63") (pinfunction "63_63") (pintype "passive"))
    )
    (net (code "125") (name "unconnected-(J4-Pad64)") (class "Default")
      (node (ref "J4") (pin "64") (pinfunction "64_64") (pintype "passive"))
    )
    (net (code "126") (name "unconnected-(J4-Pad65)") (class "Default")
      (node (ref "J4") (pin "65") (pinfunction "65_65") (pintype "passive"))
    )
    (net (code "127") (name "unconnected-(J4-Pad66)") (class "Default")
      (node (ref "J4") (pin "66") (pinfunction "66_66") (pintype "passive"))
    )
    (net (code "128") (name "unconnected-(J4-Pad67)") (class "Default")
      (node (ref "J4") (pin "67") (pinfunction "67_67") (pintype "passive"))
    )
    (net (code "129") (name "unconnected-(J4-Pad68)") (class "Default")
      (node (ref "J4") (pin "68") (pinfunction "68_68") (pintype "passive"))
    )
    (net (code "130") (name "unconnected-(J4-Pad69)") (class "Default")
      (node (ref "J4") (pin "69") (pinfunction "69_69") (pintype "passive"))
    )
    (net (code "131") (name "unconnected-(J4-SHIELD-PadB1)") (class "Default")
      (node (ref "J4") (pin "B1") (pinfunction "SHIELD_B1") (pintype "passive"))
    )
    (net (code "132") (name "unconnected-(J4-SHIELD-PadB2)") (class "Default")
      (node (ref "J4") (pin "B2") (pinfunction "SHIELD_B2") (pintype "passive"))
    )
    (net (code "133") (name "unconnected-(J5-Pad2)") (class "Default")
      (node (ref "J5") (pin "2") (pinfunction "2_2") (pintype "passive"))
    )
    (net (code "134") (name "unconnected-(J5-Pad3)") (class "Default")
      (node (ref "J5") (pin "3") (pinfunction "3_3") (pintype "passive"))
    )
    (net (code "135") (name "unconnected-(J5-Pad4)") (class "Default")
      (node (ref "J5") (pin "4") (pinfunction "4_4") (pintype "passive"))
    )
    (net (code "136") (name "unconnected-(J5-Pad5)") (class "Default")
      (node (ref "J5") (pin "5") (pinfunction "5_5") (pintype "passive"))
    )
    (net (code "137") (name "unconnected-(J5-Pad6)") (class "Default")
      (node (ref "J5") (pin "6") (pinfunction "6_6") (pintype "passive"))
    )
    (net (code "138") (name "unconnected-(J5-Pad7)") (class "Default")
      (node (ref "J5") (pin "7") (pinfunction "7_7") (pintype "passive"))
    )
    (net (code "139") (name "unconnected-(J5-Pad8)") (class "Default")
      (node (ref "J5") (pin "8") (pinfunction "8_8") (pintype "passive"))
    )
    (net (code "140") (name "unconnected-(J5-Pad9)") (class "Default")
      (node (ref "J5") (pin "9") (pinfunction "9_9") (pintype "passive"))
    )
    (net (code "141") (name "unconnected-(J5-Pad10)") (class "Default")
      (node (ref "J5") (pin "10") (pinfunction "10_10") (pintype "passive"))
    )
    (net (code "142") (name "unconnected-(J5-Pad11)") (class "Default")
      (node (ref "J5") (pin "11") (pinfunction "11_11") (pintype "passive"))
    )
    (net (code "143") (name "unconnected-(J5-Pad12)") (class "Default")
      (node (ref "J5") (pin "12") (pinfunction "12_12") (pintype "passive"))
    )
    (net (code "144") (name "unconnected-(J5-Pad13)") (class "Default")
      (node (ref "J5") (pin "13") (pinfunction "13_13") (pintype "passive"))
    )
    (net (code "145") (name "unconnected-(J5-Pad14)") (class "Default")
      (node (ref "J5") (pin "14") (pinfunction "14_14") (pintype "passive"))
    )
    (net (code "146") (name "unconnected-(J5-Pad15)") (class "Default")
      (node (ref "J5") (pin "15") (pinfunction "15_15") (pintype "passive"))
    )
    (net (code "147") (name "unconnected-(J5-Pad16)") (class "Default")
      (node (ref "J5") (pin "16") (pinfunction "16_16") (pintype "passive"))
    )
    (net (code "148") (name "unconnected-(J5-Pad17)") (class "Default")
      (node (ref "J5") (pin "17") (pinfunction "17_17") (pintype "passive"))
    )
    (net (code "149") (name "unconnected-(J5-Pad18)") (class "Default")
      (node (ref "J5") (pin "18") (pinfunction "18_18") (pintype "passive"))
    )
    (net (code "150") (name "unconnected-(J5-Pad19)") (class "Default")
      (node (ref "J5") (pin "19") (pinfunction "19_19") (pintype "passive"))
    )
    (net (code "151") (name "unconnected-(J5-Pad20)") (class "Default")
      (node (ref "J5") (pin "20") (pinfunction "20_20") (pintype "passive"))
    )
    (net (code "152") (name "unconnected-(J5-Pad25)") (class "Default")
      (node (ref "J5") (pin "25") (pinfunction "25_25") (pintype "passive"))
    )
    (net (code "153") (name "unconnected-(J5-Pad26)") (class "Default")
      (node (ref "J5") (pin "26") (pinfunction "26_26") (pintype "passive"))
    )
    (net (code "154") (name "unconnected-(J5-Pad27)") (class "Default")
      (node (ref "J5") (pin "27") (pinfunction "27_27") (pintype "passive"))
    )
    (net (code "155") (name "unconnected-(J5-Pad28)") (class "Default")
      (node (ref "J5") (pin "28") (pinfunction "28_28") (pintype "passive"))
    )
    (net (code "156") (name "unconnected-(J5-Pad29)") (class "Default")
      (node (ref "J5") (pin "29") (pinfunction "29_29") (pintype "passive"))
    )
    (net (code "157") (name "unconnected-(J5-Pad30)") (class "Default")
      (node (ref "J5") (pin "30") (pinfunction "30_30") (pintype "passive"))
    )
    (net (code "158") (name "unconnected-(J5-Pad31)") (class "Default")
      (node (ref "J5") (pin "31") (pinfunction "31_31") (pintype "passive"))
    )
    (net (code "159") (name "unconnected-(J5-Pad32)") (class "Default")
      (node (ref "J5") (pin "32") (pinfunction "32_32") (pintype "passive"))
    )
    (net (code "160") (name "unconnected-(J5-Pad33)") (class "Default")
      (node (ref "J5") (pin "33") (pinfunction "33_33") (pintype "passive"))
    )
    (net (code "161") (name "unconnected-(J5-Pad34)") (class "Default")
      (node (ref "J5") (pin "34") (pinfunction "34_34") (pintype "passive"))
    )
    (net (code "162") (name "unconnected-(J5-Pad36)") (class "Default")
      (node (ref "J5") (pin "36") (pinfunction "36_36") (pintype "passive"))
    )
    (net (code "163") (name "unconnected-(J5-Pad37)") (class "Default")
      (node (ref "J5") (pin "37") (pinfunction "37_37") (pintype "passive"))
    )
    (net (code "164") (name "unconnected-(J5-Pad38)") (class "Default")
      (node (ref "J5") (pin "38") (pinfunction "38_38") (pintype "passive"))
    )
    (net (code "165") (name "unconnected-(J5-Pad39)") (class "Default")
      (node (ref "J5") (pin "39") (pinfunction "39_39") (pintype "passive"))
    )
    (net (code "166") (name "unconnected-(J5-Pad40)") (class "Default")
      (node (ref "J5") (pin "40") (pinfunction "40_40") (pintype "passive"))
    )
    (net (code "167") (name "unconnected-(J5-Pad41)") (class "Default")
      (node (ref "J5") (pin "41") (pinfunction "41_41") (pintype "passive"))
    )
    (net (code "168") (name "unconnected-(J5-Pad42)") (class "Default")
      (node (ref "J5") (pin "42") (pinfunction "42_42") (pintype "passive"))
    )
    (net (code "169") (name "unconnected-(J5-Pad43)") (class "Default")
      (node (ref "J5") (pin "43") (pinfunction "43_43") (pintype "passive"))
    )
    (net (code "170") (name "unconnected-(J5-Pad44)") (class "Default")
      (node (ref "J5") (pin "44") (pinfunction "44_44") (pintype "passive"))
    )
    (net (code "171") (name "unconnected-(J5-Pad45)") (class "Default")
      (node (ref "J5") (pin "45") (pinfunction "45_45") (pintype "passive"))
    )
    (net (code "172") (name "unconnected-(J5-Pad46)") (class "Default")
      (node (ref "J5") (pin "46") (pinfunction "46_46") (pintype "passive"))
    )
    (net (code "173") (name "unconnected-(J5-Pad47)") (class "Default")
      (node (ref "J5") (pin "47") (pinfunction "47_47") (pintype "passive"))
    )
    (net (code "174") (name "unconnected-(J5-Pad48)") (class "Default")
      (node (ref "J5") (pin "48") (pinfunction "48_48") (pintype "passive"))
    )
    (net (code "175") (name "unconnected-(J5-Pad49)") (class "Default")
      (node (ref "J5") (pin "49") (pinfunction "49_49") (pintype "passive"))
    )
    (net (code "176") (name "unconnected-(J5-Pad50)") (class "Default")
      (node (ref "J5") (pin "50") (pinfunction "50_50") (pintype "passive"))
    )
    (net (code "177") (name "unconnected-(J5-Pad51)") (class "Default")
      (node (ref "J5") (pin "51") (pinfunction "51_51") (pintype "passive"))
    )
    (net (code "178") (name "unconnected-(J5-Pad52)") (class "Default")
      (node (ref "J5") (pin "52") (pinfunction "52_52") (pintype "passive"))
    )
    (net (code "179") (name "unconnected-(J5-Pad53)") (class "Default")
      (node (ref "J5") (pin "53") (pinfunction "53_53") (pintype "passive"))
    )
    (net (code "180") (name "unconnected-(J5-Pad54)") (class "Default")
      (node (ref "J5") (pin "54") (pinfunction "54_54") (pintype "passive"))
    )
    (net (code "181") (name "unconnected-(J5-Pad55)") (class "Default")
      (node (ref "J5") (pin "55") (pinfunction "55_55") (pintype "passive"))
    )
    (net (code "182") (name "unconnected-(J5-Pad56)") (class "Default")
      (node (ref "J5") (pin "56") (pinfunction "56_56") (pintype "passive"))
    )
    (net (code "183") (name "unconnected-(J5-Pad57)") (class "Default")
      (node (ref "J5") (pin "57") (pinfunction "57_57") (pintype "passive"))
    )
    (net (code "184") (name "unconnected-(J5-Pad58)") (class "Default")
      (node (ref "J5") (pin "58") (pinfunction "58_58") (pintype "passive"))
    )
    (net (code "185") (name "unconnected-(J5-Pad59)") (class "Default")
      (node (ref "J5") (pin "59") (pinfunction "59_59") (pintype "passive"))
    )
    (net (code "186") (name "unconnected-(J5-Pad60)") (class "Default")
      (node (ref "J5") (pin "60") (pinfunction "60_60") (pintype "passive"))
    )
    (net (code "187") (name "unconnected-(J5-Pad61)") (class "Default")
      (node (ref "J5") (pin "61") (pinfunction "61_61") (pintype "passive"))
    )
    (net (code "188") (name "unconnected-(J5-Pad62)") (class "Default")
      (node (ref "J5") (pin "62") (pinfunction "62_62") (pintype "passive"))
    )
    (net (code "189") (name "unconnected-(J5-Pad63)") (class "Default")
      (node (ref "J5") (pin "63") (pinfunction "63_63") (pintype "passive"))
    )
    (net (code "190") (name "unconnected-(J5-Pad64)") (class "Default")
      (node (ref "J5") (pin "64") (pinfunction "64_64") (pintype "passive"))
    )
    (net (code "191") (name "unconnected-(J5-Pad65)") (class "Default")
      (node (ref "J5") (pin "65") (pinfunction "65_65") (pintype "passive"))
    )
    (net (code "192") (name "unconnected-(J5-Pad66)") (class "Default")
      (node (ref "J5") (pin "66") (pinfunction "66_66") (pintype "passive"))
    )
    (net (code "193") (name "unconnected-(J5-Pad67)") (class "Default")
      (node (ref "J5") (pin "67") (pinfunction "67_67") (pintype "passive"))
    )
    (net (code "194") (name "unconnected-(J5-Pad68)") (class "Default")
      (node (ref "J5") (pin "68") (pinfunction "68_68") (pintype "passive"))
    )
    (net (code "195") (name "unconnected-(J5-Pad69)") (class "Default")
      (node (ref "J5") (pin "69") (pinfunction "69_69") (pintype "passive"))
    )
    (net (code "196") (name "unconnected-(J5-SHIELD-PadB1)") (class "Default")
      (node (ref "J5") (pin "B1") (pinfunction "SHIELD_B1") (pintype "passive"))
    )
    (net (code "197") (name "unconnected-(J5-SHIELD-PadB2)") (class "Default")
      (node (ref "J5") (pin "B2") (pinfunction "SHIELD_B2") (pintype "passive"))
    )
    (net (code "198") (name "unconnected-(U8-DOUT-Pad23)") (class "Default")
      (node (ref "U8") (pin "23") (pinfunction "DOUT_23") (pintype "passive"))
    )
    (net (code "199") (name "unconnected-(U8-NC-Pad1)") (class "Default")
      (node (ref "U8") (pin "1") (pinfunction "NC_1") (pintype "passive"))
    )
    (net (code "200") (name "unconnected-(U8-NC-Pad2)") (class "Default")
      (node (ref "U8") (pin "2") (pinfunction "NC_2") (pintype "passive"))
    )
    (net (code "201") (name "unconnected-(U8-NC-Pad14)") (class "Default")
      (node (ref "U8") (pin "14") (pinfunction "NC_14") (pintype "passive"))
    )
    (net (code "202") (name "unconnected-(U8-NC-Pad35)") (class "Default")
      (node (ref "U8") (pin "35") (pinfunction "NC_35") (pintype "passive"))
    )
    (net (code "203") (name "unconnected-(U8-NC-Pad36)") (class "Default")
      (node (ref "U8") (pin "36") (pinfunction "NC_36") (pintype "passive"))
    )
    (net (code "204") (name "unconnected-(U8-VSS-Pad16)") (class "Default")
      (node (ref "U8") (pin "16") (pinfunction "VSS_16") (pintype "passive"))
    )
    (net (code "205") (name "unconnected-(U15-DN-Pad7)") (class "Default")
      (node (ref "U15") (pin "7") (pinfunction "DN_7") (pintype "power_in"))
    )
    (net (code "206") (name "unconnected-(U15-DP-Pad5)") (class "Default")
      (node (ref "U15") (pin "5") (pinfunction "DP_5") (pintype "power_in"))
    )
    (net (code "207") (name "unconnected-(U16-DN-Pad7)") (class "Default")
      (node (ref "U16") (pin "7") (pinfunction "DN_7") (pintype "power_in"))
    )
    (net (code "208") (name "unconnected-(U16-DP-Pad5)") (class "Default")
      (node (ref "U16") (pin "5") (pinfunction "DP_5") (pintype "power_in"))
    )
  )
)
